# MCU_-_CAN_RS485.net
KiCad netlist of a schematic drawn in Altium Designer
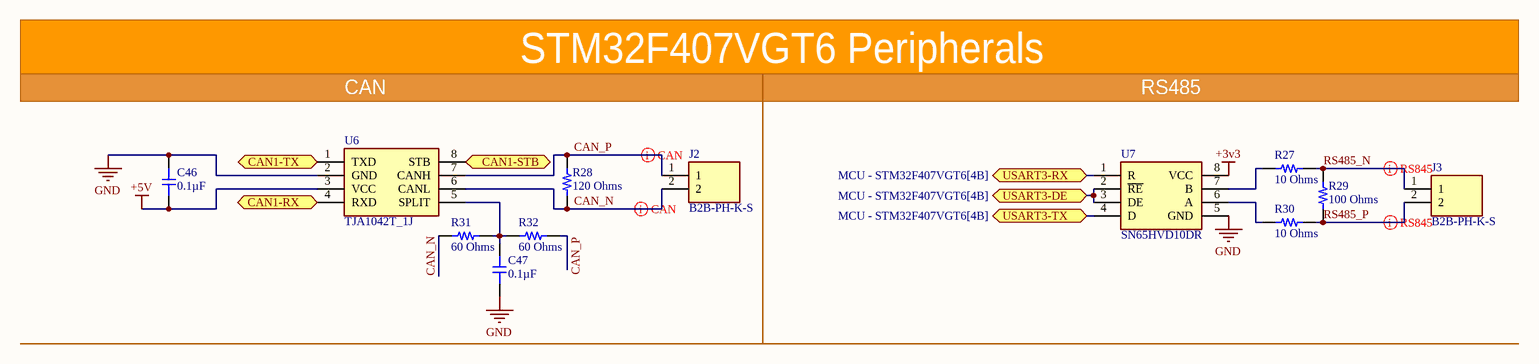
[diagram p0: MCU - CAN RS485.SchDoc]

(export (version "E")
  (design (tool "Eeschema 10.0.6"))
  (components
    (comp (ref "C46")
      (value "0.1µF")
      (footprint "0603_Footprint")
      (description "0.1uF 0603 Surface Capacitor")
      (libsource (lib "MainLibrary") (part "0.1uF 0603 Surface Capacitor"))
    )
    (comp (ref "C47")
      (value "0.1µF")
      (footprint "0603_Footprint")
      (description "0.1uF 0603 Surface Capacitor")
      (libsource (lib "MainLibrary") (part "0.1uF 0603 Surface Capacitor"))
    )
    (comp (ref "J2")
      (value "B2B-PH-K-S")
      (footprint "JST_B2B-PH-K-S")
      (description "Connector Header Through Hole 2 position 0.079 (2.00mm)")
      (fields (field (name "MF") "JST Sales America Inc."))
      (libsource (lib "MainLibrary") (part "B2B-PH-K-S"))
    )
    (comp (ref "J3")
      (value "B2B-PH-K-S")
      (footprint "JST_B2B-PH-K-S")
      (description "Connector Header Through Hole 2 position 0.079 (2.00mm)")
      (fields (field (name "MF") "JST Sales America Inc."))
      (libsource (lib "MainLibrary") (part "B2B-PH-K-S"))
    )
    (comp (ref "R27")
      (value "10 Ohms")
      (footprint "0603_RES")
      (description "10 Ohms 0603")
      (libsource (lib "MainLibrary") (part "10 Ohm 0603"))
    )
    (comp (ref "R28")
      (value "120 Ohms")
      (footprint "0603_RES")
      (description "120 Ohm 0603")
      (libsource (lib "MainLibrary") (part "120 Ohm 0603"))
    )
    (comp (ref "R29")
      (value "100 Ohms")
      (footprint "0603_RES")
      (description "100 Ohm 0603")
      (libsource (lib "MainLibrary") (part "100 Ohm 0603"))
    )
    (comp (ref "R30")
      (value "10 Ohms")
      (footprint "0603_RES")
      (description "10 Ohms 0603")
      (libsource (lib "MainLibrary") (part "10 Ohm 0603"))
    )
    (comp (ref "R31")
      (value "60 Ohms")
      (footprint "0603_RES")
      (description "60 Ohm 0603")
      (libsource (lib "MainLibrary") (part "60 Ohm 0603"))
    )
    (comp (ref "R32")
      (value "60 Ohms")
      (footprint "0603_RES")
      (description "60 Ohm 0603")
      (libsource (lib "MainLibrary") (part "60 Ohm 0603"))
    )
    (comp (ref "U6")
      (value "TJA1042T_1J")
      (footprint "ELK_H7-V2 Library:SOIC127P600X175-8N")
      (description "Integrated Circuit")
      (fields
        (field (name "MANUFACTURER_PART_NUMBER") "TJA1042T/1J")
        (field (name "MOUSER PART NUMBER") "771-TJA1042T/1J")
      )
      (libsource (lib "MainLibrary") (part "TJA1042T_1J"))
    )
    (comp (ref "U7")
      (value "SN65HVD10DR")
      (footprint "SOIC127P600X175-8N")
      (description "Integrated Circuit")
      (fields (field (name "MOUSER PART NUMBER") "595-SN65HVD10DR"))
      (libsource (lib "MainLibrary") (part "SN65HVD10DR"))
    )
  )
  (nets
    (net (code "1") (name "+3v3") (class "Default")
      (node (ref "U7") (pin "8") (pinfunction "VCC_8") (pintype "passive"))
    )
    (net (code "2") (name "+5V") (class "Default")
      (node (ref "C46") (pin "1") (pinfunction "1_1") (pintype "passive"))
      (node (ref "U6") (pin "3") (pinfunction "VCC_3") (pintype "passive"))
    )
    (net (code "3") (name "/CAN1-RX") (class "Default")
      (node (ref "U6") (pin "4") (pinfunction "RXD_4") (pintype "passive"))
    )
    (net (code "4") (name "/CAN1-STB") (class "Default")
      (node (ref "U6") (pin "8") (pinfunction "STB_8") (pintype "passive"))
    )
    (net (code "5") (name "/CAN1-TX") (class "Default")
      (node (ref "U6") (pin "1") (pinfunction "TXD_1") (pintype "passive"))
    )
    (net (code "6") (name "/CAN_N") (class "Default")
      (node (ref "J2") (pin "2") (pinfunction "2_2") (pintype "passive"))
      (node (ref "R28") (pin "1") (pinfunction "1_1") (pintype "passive"))
      (node (ref "R31") (pin "1") (pinfunction "1_1") (pintype "passive"))
      (node (ref "U6") (pin "6") (pinfunction "CANL_6") (pintype "passive"))
    )
    (net (code "7") (name "/CAN_P") (class "Default")
      (node (ref "J2") (pin "1") (pinfunction "1_1") (pintype "passive"))
      (node (ref "R28") (pin "2") (pinfunction "2_2") (pintype "passive"))
      (node (ref "R32") (pin "2") (pinfunction "2_2") (pintype "passive"))
      (node (ref "U6") (pin "7") (pinfunction "CANH_7") (pintype "passive"))
    )
    (net (code "8") (name "/RS485_N") (class "Default")
      (node (ref "J3") (pin "1") (pinfunction "1_1") (pintype "passive"))
      (node (ref "R27") (pin "2") (pinfunction "2_2") (pintype "passive"))
      (node (ref "R29") (pin "2") (pinfunction "2_2") (pintype "passive"))
    )
    (net (code "9") (name "/RS485_P") (class "Default")
      (node (ref "J3") (pin "2") (pinfunction "2_2") (pintype "passive"))
      (node (ref "R29") (pin "1") (pinfunction "1_1") (pintype "passive"))
      (node (ref "R30") (pin "2") (pinfunction "2_2") (pintype "passive"))
    )
    (net (code "10") (name "/USART3-DE") (class "Default")
      (node (ref "U7") (pin "2") (pinfunction "~{RE}_2") (pintype "passive"))
      (node (ref "U7") (pin "3") (pinfunction "DE_3") (pintype "passive"))
    )
    (net (code "11") (name "/USART3-RX") (class "Default")
      (node (ref "U7") (pin "1") (pinfunction "R_1") (pintype "passive"))
    )
    (net (code "12") (name "/USART3-TX") (class "Default")
      (node (ref "U7") (pin "4") (pinfunction "D_4") (pintype "passive"))
    )
    (net (code "13") (name "GND") (class "Default")
      (node (ref "C46") (pin "2") (pinfunction "2_2") (pintype "passive"))
      (node (ref "C47") (pin "2") (pinfunction "2_2") (pintype "passive"))
      (node (ref "U6") (pin "2") (pinfunction "GND_2") (pintype "passive"))
      (node (ref "U7") (pin "5") (pinfunction "GND_5") (pintype "passive"))
    )
    (net (code "14") (name "Net-(U6-SPLIT)") (class "Default")
      (node (ref "C47") (pin "1") (pinfunction "1_1") (pintype "passive"))
      (node (ref "R31") (pin "2") (pinfunction "2_2") (pintype "passive"))
      (node (ref "R32") (pin "1") (pinfunction "1_1") (pintype "passive"))
      (node (ref "U6") (pin "5") (pinfunction "SPLIT_5") (pintype "passive"))
    )
    (net (code "15") (name "Net-(U7-A)") (class "Default")
      (node (ref "R30") (pin "1") (pinfunction "1_1") (pintype "passive"))
      (node (ref "U7") (pin "6") (pinfunction "A_6") (pintype "passive"))
    )
    (net (code "16") (name "Net-(U7-B)") (class "Default")
      (node (ref "R27") (pin "1") (pinfunction "1_1") (pintype "passive"))
      (node (ref "U7") (pin "7") (pinfunction "B_7") (pintype "passive"))
    )
  )
)
